# PI_SCH.net
KiCad netlist of a schematic drawn in Altium Designer
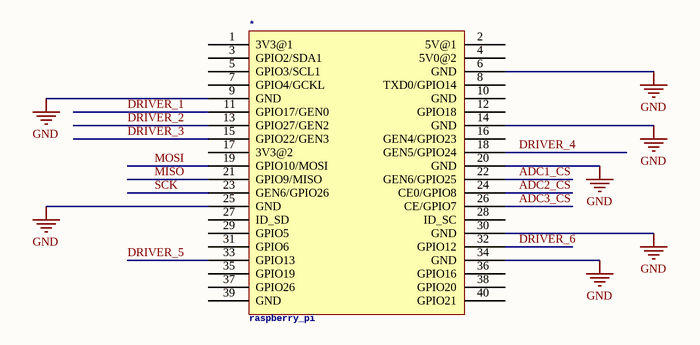
[diagram p0: PI_SCH.SchDoc]

(export (version "E")
  (design (tool "Eeschema 10.0.6"))
  (components (comp (ref "*") (value "raspberry_pi") (libsource (lib "ARCA_SCHLIB") (part "raspberry_pi"))))
  (nets
    (net (code "1") (name "/ADC1_CS") (class "Default")
      (node (ref "*") (pin "22") (pinfunction "GEN6/GPIO25_22") (pintype "passive"))
    )
    (net (code "2") (name "/ADC2_CS") (class "Default")
      (node (ref "*") (pin "24") (pinfunction "CE0/GPIO8_24") (pintype "passive"))
    )
    (net (code "3") (name "/ADC3_CS") (class "Default")
      (node (ref "*") (pin "26") (pinfunction "CE/GPIO7_26") (pintype "passive"))
    )
    (net (code "4") (name "/DRIVER_1") (class "Default")
      (node (ref "*") (pin "11") (pinfunction "GPIO17/GEN0_11") (pintype "passive"))
    )
    (net (code "5") (name "/DRIVER_2") (class "Default")
      (node (ref "*") (pin "13") (pinfunction "GPIO27/GEN2_13") (pintype "passive"))
    )
    (net (code "6") (name "/DRIVER_3") (class "Default")
      (node (ref "*") (pin "15") (pinfunction "GPIO22/GEN3_15") (pintype "passive"))
    )
    (net (code "7") (name "/DRIVER_4") (class "Default")
      (node (ref "*") (pin "18") (pinfunction "GEN5/GPIO24_18") (pintype "passive"))
    )
    (net (code "8") (name "/DRIVER_5") (class "Default")
      (node (ref "*") (pin "33") (pinfunction "GPIO13_33") (pintype "passive"))
    )
    (net (code "9") (name "/DRIVER_6") (class "Default")
      (node (ref "*") (pin "32") (pinfunction "GPIO12_32") (pintype "passive"))
    )
    (net (code "10") (name "/MISO") (class "Default")
      (node (ref "*") (pin "21") (pinfunction "GPIO9/MISO_21") (pintype "passive"))
    )
    (net (code "11") (name "/MOSI") (class "Default")
      (node (ref "*") (pin "19") (pinfunction "GPIO10/MOSI_19") (pintype "passive"))
    )
    (net (code "12") (name "/SCK") (class "Default")
      (node (ref "*") (pin "23") (pinfunction "GEN6/GPIO26_23") (pintype "passive"))
    )
    (net (code "13") (name "GND") (class "Default")
      (node (ref "*") (pin "14") (pinfunction "GND_14") (pintype "passive"))
      (node (ref "*") (pin "20") (pinfunction "GND_20") (pintype "passive"))
      (node (ref "*") (pin "25") (pinfunction "GND_25") (pintype "passive"))
      (node (ref "*") (pin "30") (pinfunction "GND_30") (pintype "passive"))
      (node (ref "*") (pin "34") (pinfunction "GND_34") (pintype "passive"))
      (node (ref "*") (pin "6") (pinfunction "GND_6") (pintype "passive"))
      (node (ref "*") (pin "9") (pinfunction "GND_9") (pintype "passive"))
    )
    (net (code "14") (name "unconnected-(*-3V3@1-Pad1)") (class "Default")
      (node (ref "*") (pin "1") (pinfunction "3V3@1_1") (pintype "passive"))
    )
    (net (code "15") (name "unconnected-(*-3V3@2-Pad17)") (class "Default")
      (node (ref "*") (pin "17") (pinfunction "3V3@2_17") (pintype "passive"))
    )
    (net (code "16") (name "unconnected-(*-5V0@2-Pad4)") (class "Default")
      (node (ref "*") (pin "4") (pinfunction "5V0@2_4") (pintype "passive"))
    )
    (net (code "17") (name "unconnected-(*-5V@1-Pad2)") (class "Default")
      (node (ref "*") (pin "2") (pinfunction "5V@1_2") (pintype "passive"))
    )
    (net (code "18") (name "unconnected-(*-GEN4{slash}GPIO23-Pad16)") (class "Default")
      (node (ref "*") (pin "16") (pinfunction "GEN4/GPIO23_16") (pintype "passive"))
    )
    (net (code "19") (name "unconnected-(*-GND-Pad10)") (class "Default")
      (node (ref "*") (pin "10") (pinfunction "GND_10") (pintype "passive"))
    )
    (net (code "20") (name "unconnected-(*-GND-Pad39)") (class "Default")
      (node (ref "*") (pin "39") (pinfunction "GND_39") (pintype "passive"))
    )
    (net (code "21") (name "unconnected-(*-GPIO2{slash}SDA1-Pad3)") (class "Default")
      (node (ref "*") (pin "3") (pinfunction "GPIO2/SDA1_3") (pintype "passive"))
    )
    (net (code "22") (name "unconnected-(*-GPIO3{slash}SCL1-Pad5)") (class "Default")
      (node (ref "*") (pin "5") (pinfunction "GPIO3/SCL1_5") (pintype "passive"))
    )
    (net (code "23") (name "unconnected-(*-GPIO4{slash}GCKL-Pad7)") (class "Default")
      (node (ref "*") (pin "7") (pinfunction "GPIO4/GCKL_7") (pintype "passive"))
    )
    (net (code "24") (name "unconnected-(*-GPIO5-Pad29)") (class "Default")
      (node (ref "*") (pin "29") (pinfunction "GPIO5_29") (pintype "passive"))
    )
    (net (code "25") (name "unconnected-(*-GPIO6-Pad31)") (class "Default")
      (node (ref "*") (pin "31") (pinfunction "GPIO6_31") (pintype "passive"))
    )
    (net (code "26") (name "unconnected-(*-GPIO16-Pad36)") (class "Default")
      (node (ref "*") (pin "36") (pinfunction "GPIO16_36") (pintype "passive"))
    )
    (net (code "27") (name "unconnected-(*-GPIO18-Pad12)") (class "Default")
      (node (ref "*") (pin "12") (pinfunction "GPIO18_12") (pintype "passive"))
    )
    (net (code "28") (name "unconnected-(*-GPIO19-Pad35)") (class "Default")
      (node (ref "*") (pin "35") (pinfunction "GPIO19_35") (pintype "passive"))
    )
    (net (code "29") (name "unconnected-(*-GPIO20-Pad38)") (class "Default")
      (node (ref "*") (pin "38") (pinfunction "GPIO20_38") (pintype "passive"))
    )
    (net (code "30") (name "unconnected-(*-GPIO21-Pad40)") (class "Default")
      (node (ref "*") (pin "40") (pinfunction "GPIO21_40") (pintype "passive"))
    )
    (net (code "31") (name "unconnected-(*-GPIO26-Pad37)") (class "Default")
      (node (ref "*") (pin "37") (pinfunction "GPIO26_37") (pintype "passive"))
    )
    (net (code "32") (name "unconnected-(*-ID_SC-Pad28)") (class "Default")
      (node (ref "*") (pin "28") (pinfunction "ID_SC_28") (pintype "passive"))
    )
    (net (code "33") (name "unconnected-(*-ID_SD-Pad27)") (class "Default")
      (node (ref "*") (pin "27") (pinfunction "ID_SD_27") (pintype "passive"))
    )
    (net (code "34") (name "unconnected-(*-TXD0{slash}GPIO14-Pad8)") (class "Default")
      (node (ref "*") (pin "8") (pinfunction "TXD0/GPIO14_8") (pintype "passive"))
    )
  )
)
